# schematic_slave1_ammonia.net
KiCad netlist of a schematic drawn in EAGLE
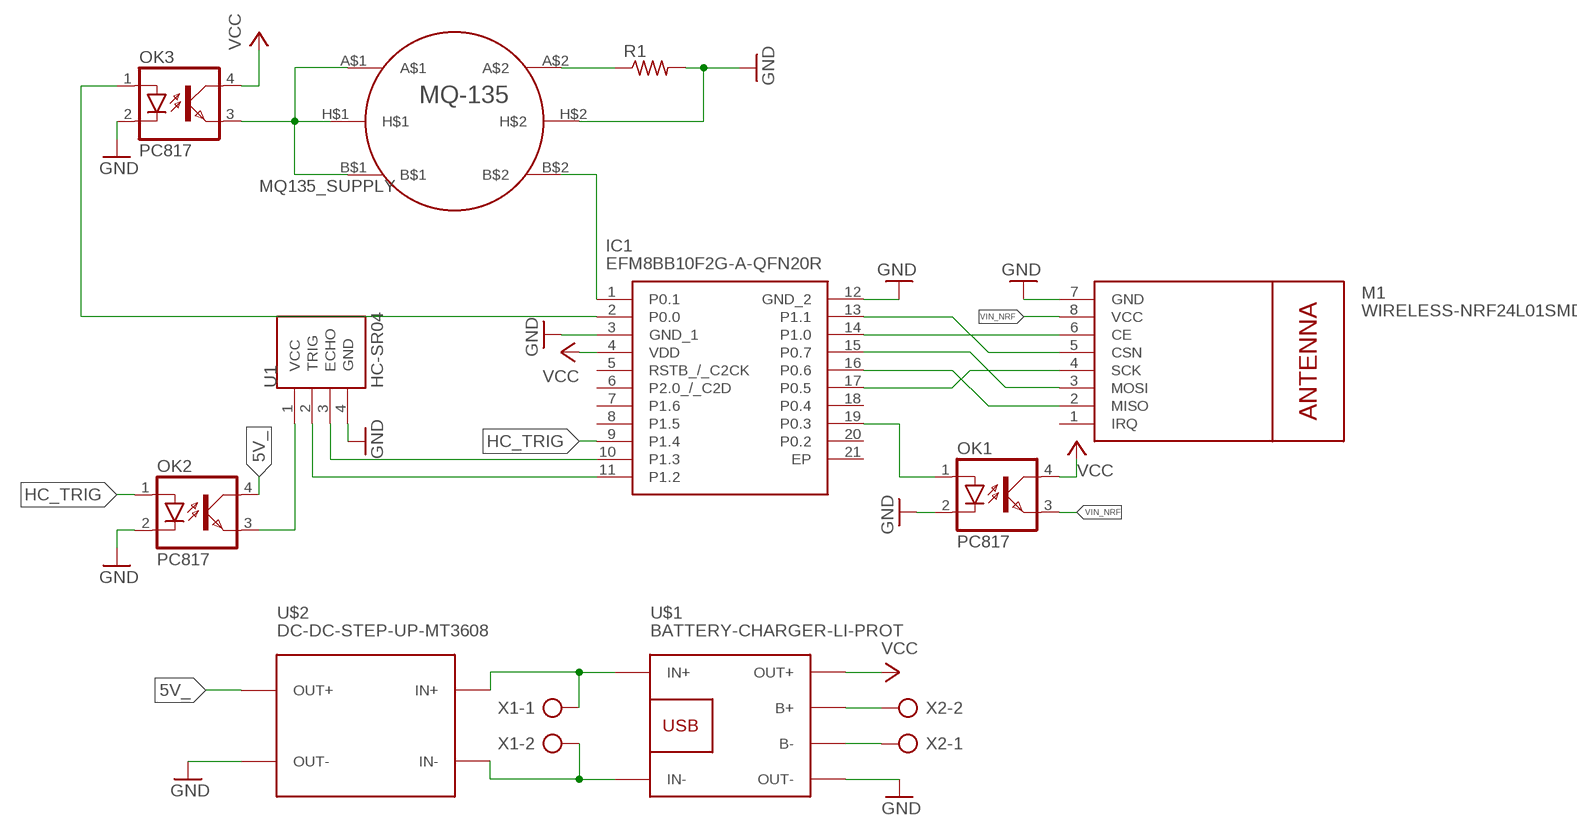
[diagram p0: schematic, sheet 1]

(export (version "E")
  (design (tool "Eeschema 10.0.6"))
  (components
    (comp (ref "IC1")
      (value "EFM8BB10F2G-A-QFN20R")
      (footprint "eagle-import:EFM8BB10F2GAQFN20R")
      (fields (field (name "MOUSER_PART_NUMBER") "634-8BB10F2GAQF20R"))
      (libsource (lib "eagle-import") (part "EFM8BB10F2G-A-QFN20R"))
    )
    (comp (ref "M1")
      (value "WIRELESS-NRF24L01SMD")
      (footprint "eagle-import:WIRELESS-NRF24L01-SMD")
      (libsource (lib "eagle-import") (part "WIRELESS-NRF24L01SMD"))
    )
    (comp (ref "OK1")
      (value "PC817")
      (footprint "eagle-import:DIL04")
      (fields (field (name "MPN") "PC817X4J000F"))
      (libsource (lib "eagle-import") (part "PC817"))
    )
    (comp (ref "OK2")
      (value "PC817")
      (footprint "eagle-import:DIL04")
      (fields (field (name "MPN") "PC817X4J000F"))
      (libsource (lib "eagle-import") (part "PC817"))
    )
    (comp (ref "OK3")
      (value "PC817")
      (footprint "eagle-import:DIL04")
      (fields (field (name "MPN") "PC817X4J000F"))
      (libsource (lib "eagle-import") (part "PC817"))
    )
    (comp (ref "R1")
      (value "R-US_R0805")
      (footprint "eagle-import:R0805")
      (libsource (lib "eagle-import") (part "R-US_R0805"))
    )
    (comp (ref "U$1")
      (value "BATTERY-CHARGER-LI-PROT")
      (footprint "eagle-import:BATTERY-CHARGER-LI-PROT")
      (libsource (lib "eagle-import") (part "BATTERY-CHARGER-LI-PROT"))
    )
    (comp (ref "U$2")
      (value "DC-DC-STEP-UP-MT3608")
      (footprint "eagle-import:DC-DC-STEP-UP-MT3608")
      (libsource (lib "eagle-import") (part "DC-DC-STEP-UP-MT3608"))
    )
    (comp (ref "U$3")
      (value "MQ_135_A")
      (footprint "eagle-import:MQ-135")
      (libsource (lib "eagle-import") (part "MQ_135_A"))
    )
    (comp (ref "U1")
      (value "HC-SR04")
      (footprint "eagle-import:XCVR_HC-SR04")
      (fields (field (name "MF") "SparkFun Electronics"))
      (libsource (lib "eagle-import") (part "HC-SR04"))
    )
    (comp (ref "X1")
      (value "AK500/2-H")
      (footprint "eagle-import:AK500_2-H")
      (libsource (lib "eagle-import") (part "AK500/2-H"))
    )
    (comp (ref "X2")
      (value "AK500/2-H")
      (footprint "eagle-import:AK500_2-H")
      (libsource (lib "eagle-import") (part "AK500/2-H"))
    )
  )
  (nets
    (net (code "1") (name "/MQ135_SUPPLY") (class "Default")
      (node (ref "OK3") (pin "3") (pinfunction "EMIT_3") (pintype "passive"))
      (node (ref "U$3") (pin "A$1") (pinfunction "A$1_A$1") (pintype "bidirectional"))
      (node (ref "U$3") (pin "B$1") (pinfunction "B$1_B$1") (pintype "bidirectional"))
      (node (ref "U$3") (pin "H$1") (pinfunction "H$1_H$1") (pintype "bidirectional"))
    )
    (net (code "2") (name "5V_") (class "Default")
      (node (ref "OK2") (pin "4") (pinfunction "COL_4") (pintype "passive"))
      (node (ref "U$2") (pin "OUT+") (pinfunction "OUT+_OUT+") (pintype "bidirectional"))
    )
    (net (code "3") (name "GND") (class "Default")
      (node (ref "IC1") (pin "12") (pinfunction "GND_2_12") (pintype "bidirectional"))
      (node (ref "IC1") (pin "3") (pinfunction "GND_1_3") (pintype "bidirectional"))
      (node (ref "M1") (pin "7") (pinfunction "GND_7") (pintype "power_in"))
      (node (ref "OK1") (pin "2") (pinfunction "C_2") (pintype "passive"))
      (node (ref "OK2") (pin "2") (pinfunction "C_2") (pintype "passive"))
      (node (ref "OK3") (pin "2") (pinfunction "C_2") (pintype "passive"))
      (node (ref "R1") (pin "2") (pinfunction "2_2") (pintype "passive"))
      (node (ref "U$1") (pin "OUT-") (pinfunction "OUT-_OUT-") (pintype "bidirectional"))
      (node (ref "U$2") (pin "OUT-") (pinfunction "OUT-_OUT-") (pintype "bidirectional"))
      (node (ref "U$3") (pin "H$2") (pinfunction "H$2_H$2") (pintype "bidirectional"))
      (node (ref "U1") (pin "4") (pinfunction "GND_4") (pintype "power_in"))
    )
    (net (code "4") (name "HC_TRIG") (class "Default")
      (node (ref "IC1") (pin "2") (pinfunction "P0.0_2") (pintype "bidirectional"))
      (node (ref "IC1") (pin "9") (pinfunction "P1.4_9") (pintype "bidirectional"))
      (node (ref "OK2") (pin "1") (pinfunction "A_1") (pintype "passive"))
      (node (ref "OK3") (pin "1") (pinfunction "A_1") (pintype "passive"))
    )
    (net (code "5") (name "Net-(IC1-P0.1)") (class "Default")
      (node (ref "IC1") (pin "1") (pinfunction "P0.1_1") (pintype "bidirectional"))
      (node (ref "U$3") (pin "B$2") (pinfunction "B$2_B$2") (pintype "bidirectional"))
    )
    (net (code "6") (name "Net-(IC1-P0.3)") (class "Default")
      (node (ref "IC1") (pin "19") (pinfunction "P0.3_19") (pintype "bidirectional"))
      (node (ref "OK1") (pin "1") (pinfunction "A_1") (pintype "passive"))
    )
    (net (code "7") (name "Net-(IC1-P0.5)") (class "Default")
      (node (ref "IC1") (pin "17") (pinfunction "P0.5_17") (pintype "bidirectional"))
      (node (ref "M1") (pin "4") (pinfunction "SCK_4") (pintype "bidirectional"))
    )
    (net (code "8") (name "Net-(IC1-P0.6)") (class "Default")
      (node (ref "IC1") (pin "16") (pinfunction "P0.6_16") (pintype "bidirectional"))
      (node (ref "M1") (pin "2") (pinfunction "MISO_2") (pintype "bidirectional"))
    )
    (net (code "9") (name "Net-(IC1-P0.7)") (class "Default")
      (node (ref "IC1") (pin "15") (pinfunction "P0.7_15") (pintype "bidirectional"))
      (node (ref "M1") (pin "3") (pinfunction "MOSI_3") (pintype "bidirectional"))
    )
    (net (code "10") (name "Net-(IC1-P1.0)") (class "Default")
      (node (ref "IC1") (pin "14") (pinfunction "P1.0_14") (pintype "bidirectional"))
      (node (ref "M1") (pin "6") (pinfunction "CE_6") (pintype "bidirectional"))
    )
    (net (code "11") (name "Net-(IC1-P1.1)") (class "Default")
      (node (ref "IC1") (pin "13") (pinfunction "P1.1_13") (pintype "bidirectional"))
      (node (ref "M1") (pin "5") (pinfunction "CSN_5") (pintype "bidirectional"))
    )
    (net (code "12") (name "Net-(IC1-P1.2)") (class "Default")
      (node (ref "IC1") (pin "11") (pinfunction "P1.2_11") (pintype "bidirectional"))
      (node (ref "U1") (pin "2") (pinfunction "TRIG_2") (pintype "bidirectional"))
    )
    (net (code "13") (name "Net-(IC1-P1.3)") (class "Default")
      (node (ref "IC1") (pin "10") (pinfunction "P1.3_10") (pintype "bidirectional"))
      (node (ref "U1") (pin "3") (pinfunction "ECHO_3") (pintype "bidirectional"))
    )
    (net (code "14") (name "Net-(OK2-EMIT)") (class "Default")
      (node (ref "OK2") (pin "3") (pinfunction "EMIT_3") (pintype "passive"))
      (node (ref "U1") (pin "1") (pinfunction "VCC_1") (pintype "power_in"))
    )
    (net (code "15") (name "Net-(R1-Pad1)") (class "Default")
      (node (ref "R1") (pin "1") (pinfunction "1_1") (pintype "passive"))
      (node (ref "U$3") (pin "A$2") (pinfunction "A$2_A$2") (pintype "bidirectional"))
    )
    (net (code "16") (name "Net-(X1A-KL)") (class "Default")
      (node (ref "U$1") (pin "IN+") (pinfunction "IN+_IN+") (pintype "bidirectional"))
      (node (ref "U$2") (pin "IN+") (pinfunction "IN+_IN+") (pintype "bidirectional"))
      (node (ref "X1") (pin "1") (pinfunction "KL_1") (pintype "passive"))
    )
    (net (code "17") (name "Net-(X1B-KL)") (class "Default")
      (node (ref "U$1") (pin "IN-") (pinfunction "IN-_IN-") (pintype "bidirectional"))
      (node (ref "U$2") (pin "IN-") (pinfunction "IN-_IN-") (pintype "bidirectional"))
      (node (ref "X1") (pin "2") (pinfunction "KL_2") (pintype "passive"))
    )
    (net (code "18") (name "Net-(X2A-KL)") (class "Default")
      (node (ref "U$1") (pin "B-") (pinfunction "B-_B-") (pintype "bidirectional"))
      (node (ref "X2") (pin "1") (pinfunction "KL_1") (pintype "passive"))
    )
    (net (code "19") (name "Net-(X2B-KL)") (class "Default")
      (node (ref "U$1") (pin "B+") (pinfunction "B+_B+") (pintype "bidirectional"))
      (node (ref "X2") (pin "2") (pinfunction "KL_2") (pintype "passive"))
    )
    (net (code "20") (name "VCC") (class "Default")
      (node (ref "IC1") (pin "4") (pinfunction "VDD_4") (pintype "bidirectional"))
      (node (ref "OK1") (pin "4") (pinfunction "COL_4") (pintype "passive"))
      (node (ref "OK3") (pin "4") (pinfunction "COL_4") (pintype "passive"))
      (node (ref "U$1") (pin "OUT+") (pinfunction "OUT+_OUT+") (pintype "bidirectional"))
    )
    (net (code "21") (name "VIN_NRF") (class "Default")
      (node (ref "M1") (pin "8") (pinfunction "VCC_8") (pintype "power_in"))
      (node (ref "OK1") (pin "3") (pinfunction "EMIT_3") (pintype "passive"))
    )
    (net (code "22") (name "unconnected-(IC1-EP-Pad21)") (class "Default")
      (node (ref "IC1") (pin "21") (pinfunction "EP_21") (pintype "bidirectional"))
    )
    (net (code "23") (name "unconnected-(IC1-P0.2-Pad20)") (class "Default")
      (node (ref "IC1") (pin "20") (pinfunction "P0.2_20") (pintype "bidirectional"))
    )
    (net (code "24") (name "unconnected-(IC1-P0.4-Pad18)") (class "Default")
      (node (ref "IC1") (pin "18") (pinfunction "P0.4_18") (pintype "bidirectional"))
    )
    (net (code "25") (name "unconnected-(IC1-P1.5-Pad8)") (class "Default")
      (node (ref "IC1") (pin "8") (pinfunction "P1.5_8") (pintype "bidirectional"))
    )
    (net (code "26") (name "unconnected-(IC1-P1.6-Pad7)") (class "Default")
      (node (ref "IC1") (pin "7") (pinfunction "P1.6_7") (pintype "bidirectional"))
    )
    (net (code "27") (name "unconnected-(IC1-P2.0_{slash}_C2D-Pad6)") (class "Default")
      (node (ref "IC1") (pin "6") (pinfunction "P2.0_/_C2D_6") (pintype "bidirectional"))
    )
    (net (code "28") (name "unconnected-(IC1-RSTB_{slash}_C2CK-Pad5)") (class "Default")
      (node (ref "IC1") (pin "5") (pinfunction "RSTB_/_C2CK_5") (pintype "bidirectional"))
    )
    (net (code "29") (name "unconnected-(M1-IRQ-Pad1)") (class "Default")
      (node (ref "M1") (pin "1") (pinfunction "IRQ_1") (pintype "bidirectional"))
    )
  )
)
